# UARTBreakout-3_0.net
KiCad netlist of a schematic drawn in EAGLE
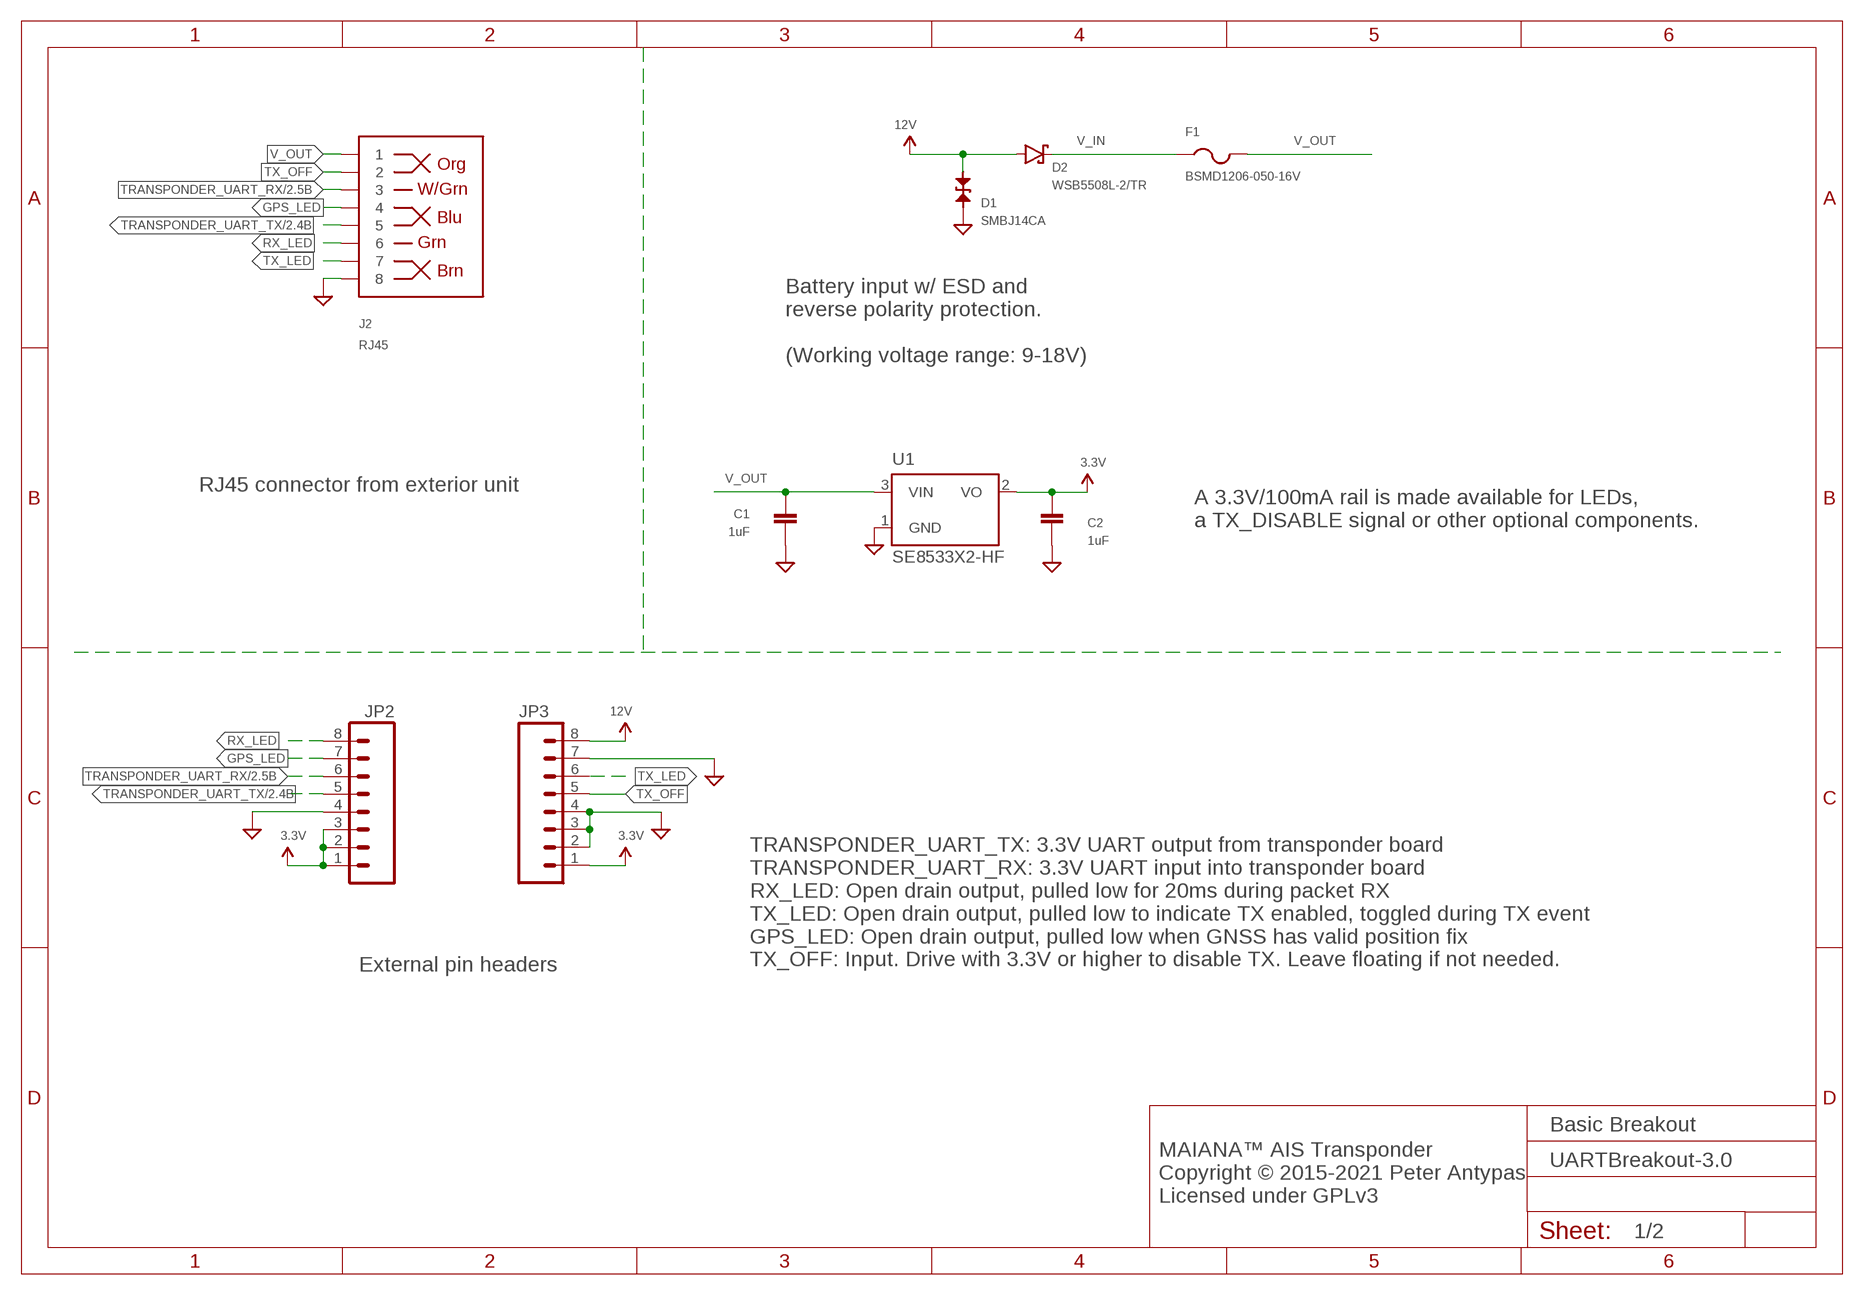
[diagram p0: schematic, sheet 1]
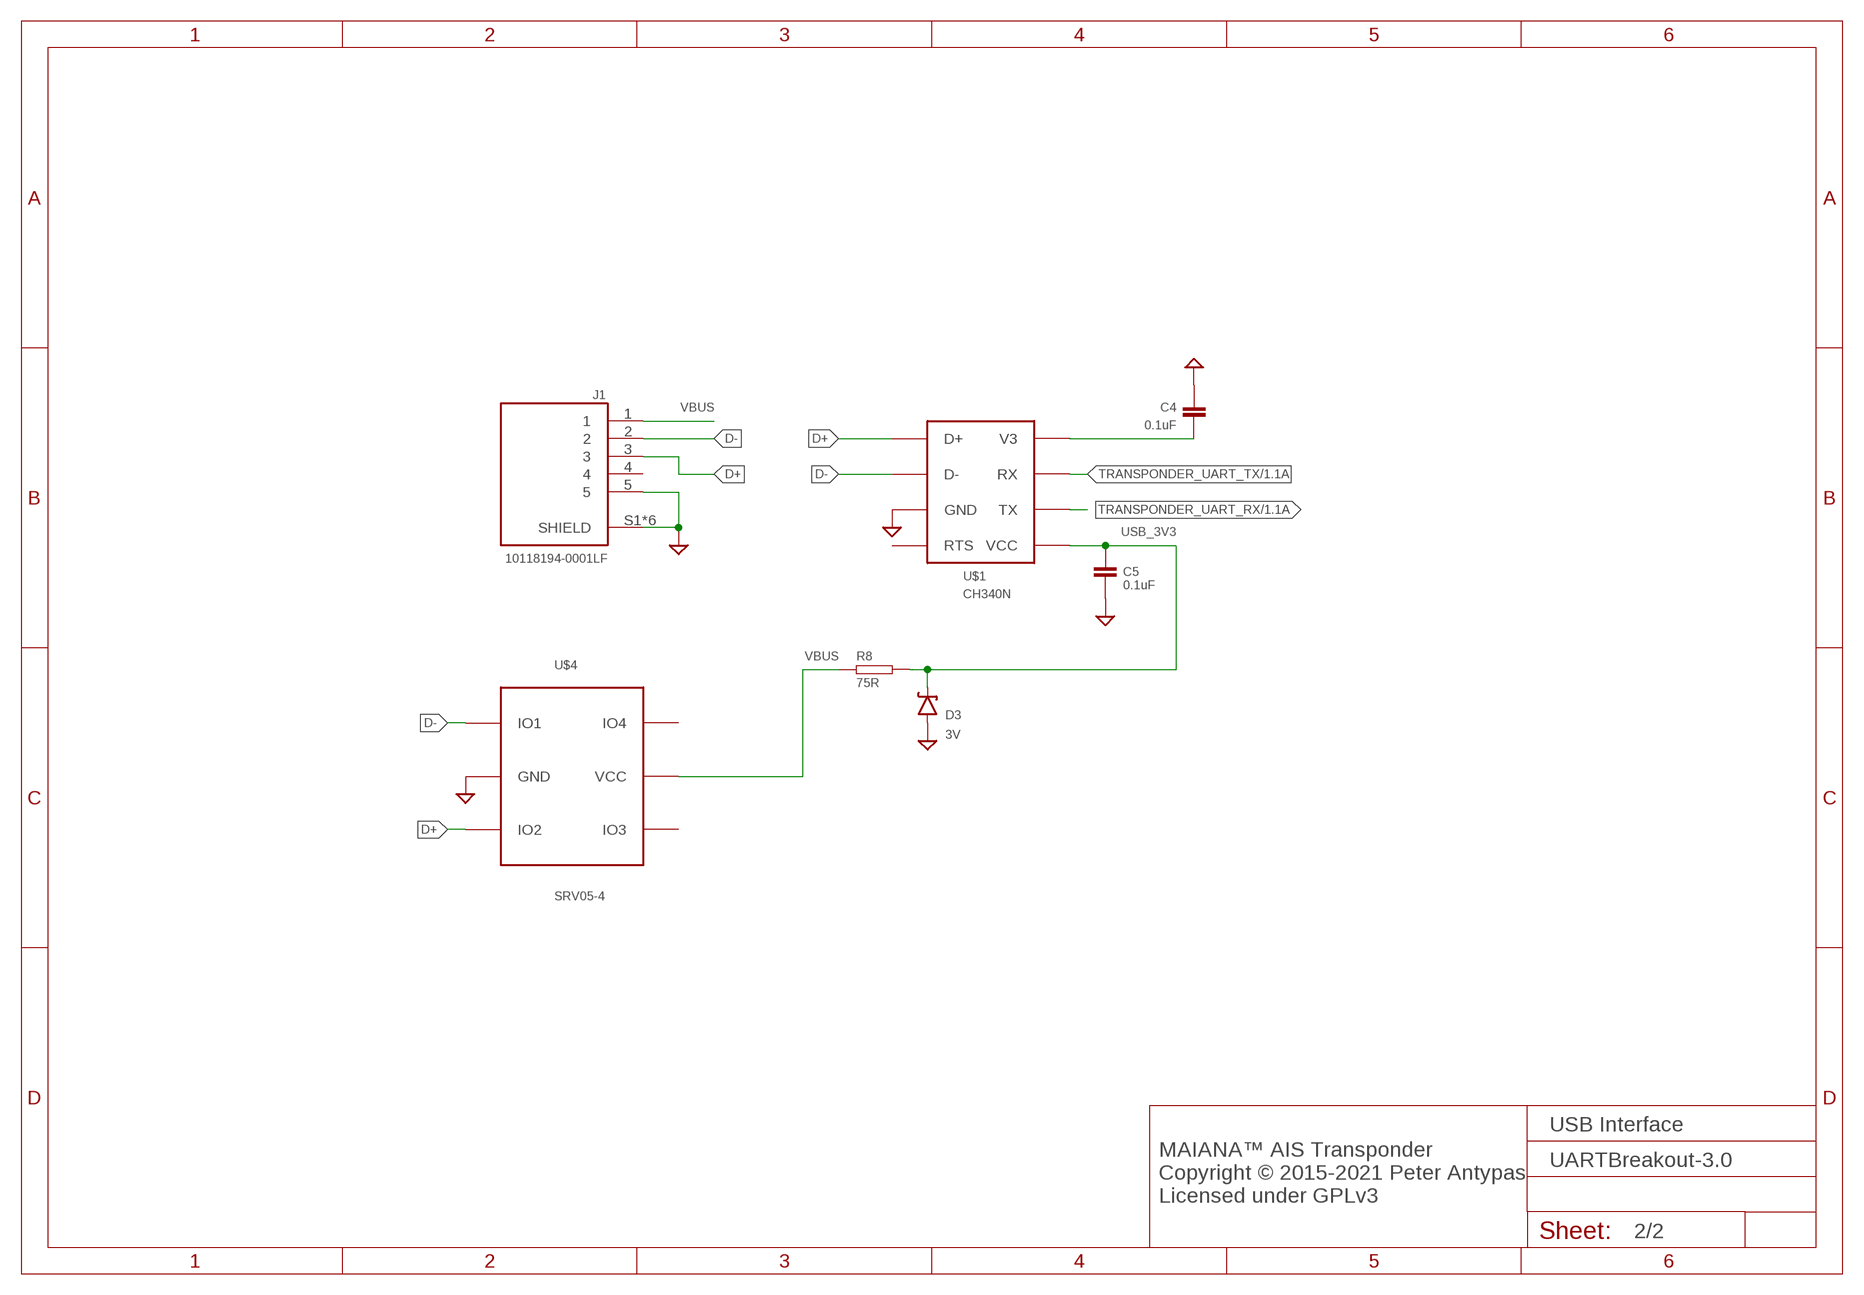
[diagram p1: schematic, sheet 2]

(export (version "E")
  (design (tool "Eeschema 10.0.6"))
  (components
    (comp (ref "C1")
      (value "1uF")
      (footprint "eagle-import:0603")
      (fields (field (name "PARTNO") "CC0603KRX5R8BB105"))
      (libsource (lib "eagle-import") (part "CAPACITOR0603"))
    )
    (comp (ref "C2")
      (value "1uF")
      (footprint "eagle-import:0603")
      (fields (field (name "PARTNO") "CC0603KRX5R8BB105"))
      (libsource (lib "eagle-import") (part "CAPACITOR0603"))
    )
    (comp (ref "D1")
      (value "SMBJ14CA")
      (footprint "eagle-import:SMB-BIDIR")
      (fields (field (name "PARTNO") "SMBJ14CA"))
      (libsource (lib "eagle-import") (part "DIODE-TVS-BIDIRSMB"))
    )
    (comp (ref "D2")
      (value "WSB5508L-2/TR")
      (footprint "eagle-import:SOD123")
      (fields (field (name "PARTNO") "WSB5508L-2/TR"))
      (libsource (lib "eagle-import") (part "DIODE-SCHOTTKYSOD123"))
    )
    (comp (ref "F1")
      (value "BSMD1206-050-16V")
      (footprint "eagle-import:R1206")
      (libsource (lib "eagle-import") (part "PTCFUSE-1206"))
    )
    (comp (ref "J2")
      (value "RJ45")
      (footprint "eagle-import:RJ45-8")
      (fields (field (name "PARTNO") "95501-2821"))
      (libsource (lib "eagle-import") (part "RJ45-8PTH"))
    )
    (comp (ref "JP2")
      (value "M08SILK_FEMALE_PTH")
      (footprint "eagle-import:1X08")
      (libsource (lib "eagle-import") (part "M08SILK_FEMALE_PTH"))
    )
    (comp (ref "JP3")
      (value "M08SILK_FEMALE_PTH")
      (footprint "eagle-import:1X08")
      (libsource (lib "eagle-import") (part "M08SILK_FEMALE_PTH"))
    )
    (comp (ref "U1")
      (value "SE8533X2-HF")
      (footprint "eagle-import:SOT23")
      (libsource (lib "eagle-import") (part "MCP1799T"))
    )
    (comp (ref "C4")
      (value "0.1uF")
      (footprint "eagle-import:0603")
      (libsource (lib "eagle-import") (part "CAPACITOR0603"))
    )
    (comp (ref "C5")
      (value "0.1uF")
      (footprint "eagle-import:0603")
      (libsource (lib "eagle-import") (part "CAPACITOR0603"))
    )
    (comp (ref "D3")
      (value "3V")
      (footprint "eagle-import:SOD-323")
      (libsource (lib "eagle-import") (part "DIODE-ZENER3.3V"))
    )
    (comp (ref "J1")
      (value "10118194-0001LF")
      (footprint "eagle-import:AMPHENOL_10118194-0001LF")
      (fields (field (name "MF") "Amphenol ICC (FCI)"))
      (libsource (lib "eagle-import") (part "10118194-0001LF"))
    )
    (comp (ref "R8")
      (value "75R")
      (footprint "eagle-import:0603")
      (libsource (lib "eagle-import") (part "RESISTOR0603"))
    )
    (comp (ref "U$1")
      (value "CH340N")
      (footprint "eagle-import:SOIC-8")
      (libsource (lib "eagle-import") (part "CH330N"))
    )
    (comp (ref "U$4")
      (value "SRV05-4")
      (footprint "eagle-import:SOT23-6")
      (libsource (lib "eagle-import") (part "SRV05-4"))
    )
  )
  (nets
    (net (code "1") (name "3.3V") (class "Default")
      (node (ref "C2") (pin "P$1") (pinfunction "1_P$1") (pintype "passive"))
      (node (ref "JP2") (pin "1") (pinfunction "1_1") (pintype "passive"))
      (node (ref "JP2") (pin "2") (pinfunction "2_2") (pintype "passive"))
      (node (ref "JP2") (pin "3") (pinfunction "3_3") (pintype "passive"))
      (node (ref "JP3") (pin "1") (pinfunction "1_1") (pintype "passive"))
      (node (ref "U1") (pin "2") (pinfunction "VO_2") (pintype "output"))
    )
    (net (code "2") (name "12V") (class "Default")
      (node (ref "D1") (pin "A") (pinfunction "P$1_A") (pintype "bidirectional"))
      (node (ref "D2") (pin "A") (pinfunction "A_A") (pintype "passive"))
      (node (ref "JP3") (pin "8") (pinfunction "8_8") (pintype "passive"))
    )
    (net (code "3") (name "D+") (class "Default")
      (node (ref "J1") (pin "3") (pinfunction "3_3") (pintype "passive"))
      (node (ref "U$1") (pin "1") (pinfunction "D+_1") (pintype "bidirectional"))
      (node (ref "U$4") (pin "3") (pinfunction "IO2_3") (pintype "bidirectional"))
    )
    (net (code "4") (name "D-") (class "Default")
      (node (ref "J1") (pin "2") (pinfunction "2_2") (pintype "passive"))
      (node (ref "U$1") (pin "2") (pinfunction "D-_2") (pintype "bidirectional"))
      (node (ref "U$4") (pin "1") (pinfunction "IO1_1") (pintype "bidirectional"))
    )
    (net (code "5") (name "GND") (class "Default")
      (node (ref "C1") (pin "P$2") (pinfunction "2_P$2") (pintype "passive"))
      (node (ref "C2") (pin "P$2") (pinfunction "2_P$2") (pintype "passive"))
      (node (ref "C4") (pin "P$2") (pinfunction "2_P$2") (pintype "passive"))
      (node (ref "C5") (pin "P$2") (pinfunction "2_P$2") (pintype "passive"))
      (node (ref "D1") (pin "C") (pinfunction "P$2_C") (pintype "bidirectional"))
      (node (ref "D3") (pin "A") (pinfunction "A_A") (pintype "passive"))
      (node (ref "J1") (pin "5") (pinfunction "5_5") (pintype "passive"))
      (node (ref "J1") (pin "S1") (pinfunction "SHIELD_S1") (pintype "passive"))
      (node (ref "J1") (pin "S2") (pinfunction "SHIELD_S2") (pintype "passive"))
      (node (ref "J1") (pin "S3") (pinfunction "SHIELD_S3") (pintype "passive"))
      (node (ref "J1") (pin "S4") (pinfunction "SHIELD_S4") (pintype "passive"))
      (node (ref "J1") (pin "S5") (pinfunction "SHIELD_S5") (pintype "passive"))
      (node (ref "J1") (pin "S6") (pinfunction "SHIELD_S6") (pintype "passive"))
      (node (ref "J2") (pin "8") (pinfunction "8_8") (pintype "bidirectional"))
      (node (ref "JP2") (pin "4") (pinfunction "4_4") (pintype "passive"))
      (node (ref "JP3") (pin "2") (pinfunction "2_2") (pintype "passive"))
      (node (ref "JP3") (pin "3") (pinfunction "3_3") (pintype "passive"))
      (node (ref "JP3") (pin "4") (pinfunction "4_4") (pintype "passive"))
      (node (ref "JP3") (pin "7") (pinfunction "7_7") (pintype "passive"))
      (node (ref "U$1") (pin "3") (pinfunction "GND_3") (pintype "bidirectional"))
      (node (ref "U$4") (pin "2") (pinfunction "GND_2") (pintype "bidirectional"))
      (node (ref "U1") (pin "1") (pinfunction "GND_1") (pintype "passive"))
    )
    (net (code "6") (name "GPS_LED") (class "Default")
      (node (ref "J2") (pin "4") (pinfunction "4_4") (pintype "bidirectional"))
      (node (ref "JP2") (pin "7") (pinfunction "7_7") (pintype "passive"))
    )
    (net (code "7") (name "Net-(C4-1)") (class "Default")
      (node (ref "C4") (pin "P$1") (pinfunction "1_P$1") (pintype "passive"))
      (node (ref "U$1") (pin "8") (pinfunction "V3_8") (pintype "bidirectional"))
    )
    (net (code "8") (name "RX_LED") (class "Default")
      (node (ref "J2") (pin "6") (pinfunction "6_6") (pintype "bidirectional"))
      (node (ref "JP2") (pin "8") (pinfunction "8_8") (pintype "passive"))
    )
    (net (code "9") (name "TRANSPONDER_UART_RX") (class "Default")
      (node (ref "J2") (pin "3") (pinfunction "3_3") (pintype "bidirectional"))
      (node (ref "JP2") (pin "6") (pinfunction "6_6") (pintype "passive"))
      (node (ref "U$1") (pin "6") (pinfunction "TX_6") (pintype "bidirectional"))
    )
    (net (code "10") (name "TRANSPONDER_UART_TX") (class "Default")
      (node (ref "J2") (pin "5") (pinfunction "5_5") (pintype "bidirectional"))
      (node (ref "JP2") (pin "5") (pinfunction "5_5") (pintype "passive"))
      (node (ref "U$1") (pin "7") (pinfunction "RX_7") (pintype "bidirectional"))
    )
    (net (code "11") (name "TX_LED") (class "Default")
      (node (ref "J2") (pin "7") (pinfunction "7_7") (pintype "bidirectional"))
      (node (ref "JP3") (pin "6") (pinfunction "6_6") (pintype "passive"))
    )
    (net (code "12") (name "TX_OFF") (class "Default")
      (node (ref "J2") (pin "2") (pinfunction "2_2") (pintype "bidirectional"))
      (node (ref "JP3") (pin "5") (pinfunction "5_5") (pintype "passive"))
    )
    (net (code "13") (name "USB_3V3") (class "Default")
      (node (ref "C5") (pin "P$1") (pinfunction "1_P$1") (pintype "passive"))
      (node (ref "D3") (pin "C") (pinfunction "C_C") (pintype "passive"))
      (node (ref "R8") (pin "P$2") (pinfunction "P$2_P$2") (pintype "passive"))
      (node (ref "U$1") (pin "5") (pinfunction "VCC_5") (pintype "bidirectional"))
    )
    (net (code "14") (name "VBUS") (class "Default")
      (node (ref "J1") (pin "1") (pinfunction "1_1") (pintype "passive"))
      (node (ref "R8") (pin "P$1") (pinfunction "P$1_P$1") (pintype "passive"))
      (node (ref "U$4") (pin "5") (pinfunction "VCC_5") (pintype "bidirectional"))
    )
    (net (code "15") (name "V_IN") (class "Default")
      (node (ref "D2") (pin "C") (pinfunction "C_C") (pintype "passive"))
      (node (ref "F1") (pin "1") (pinfunction "1_1") (pintype "passive"))
    )
    (net (code "16") (name "V_OUT") (class "Default")
      (node (ref "C1") (pin "P$1") (pinfunction "1_P$1") (pintype "passive"))
      (node (ref "F1") (pin "2") (pinfunction "2_2") (pintype "passive"))
      (node (ref "J2") (pin "1") (pinfunction "1_1") (pintype "bidirectional"))
      (node (ref "U1") (pin "3") (pinfunction "VIN_3") (pintype "input"))
    )
    (net (code "17") (name "unconnected-(J1-Pad4)") (class "Default")
      (node (ref "J1") (pin "4") (pinfunction "4_4") (pintype "passive"))
    )
    (net (code "18") (name "unconnected-(U$1-RTS-Pad4)") (class "Default")
      (node (ref "U$1") (pin "4") (pinfunction "RTS_4") (pintype "bidirectional"))
    )
    (net (code "19") (name "unconnected-(U$4-IO3-Pad4)") (class "Default")
      (node (ref "U$4") (pin "4") (pinfunction "IO3_4") (pintype "bidirectional"))
    )
    (net (code "20") (name "unconnected-(U$4-IO4-Pad6)") (class "Default")
      (node (ref "U$4") (pin "6") (pinfunction "IO4_6") (pintype "bidirectional"))
    )
  )
)
